# MineSweepers2019-Communcation.net
KiCad netlist of a schematic drawn in EAGLE
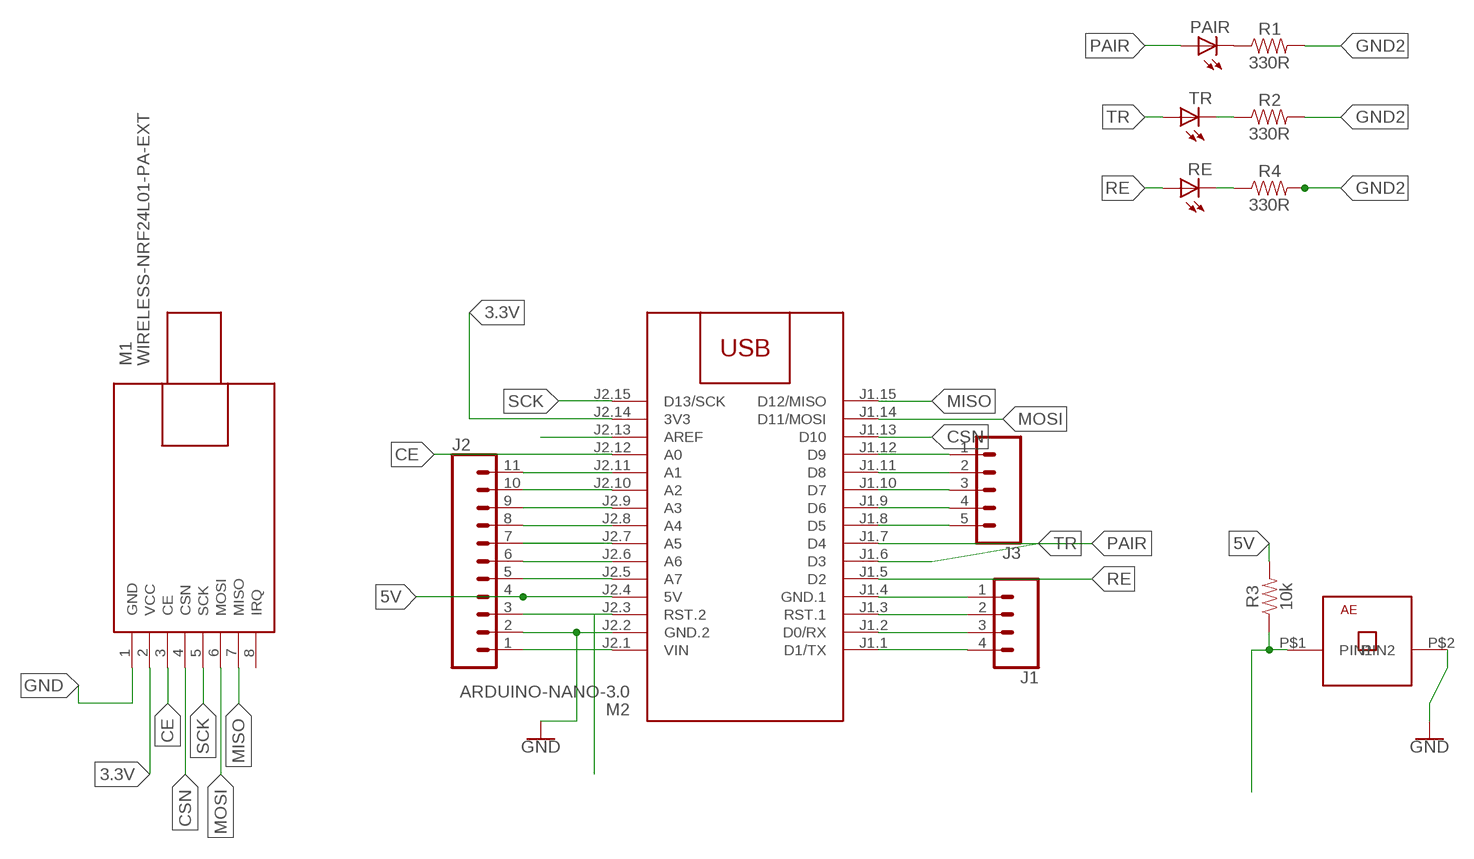
[diagram p0: schematic, sheet 1]

(export (version "E")
  (design (tool "Eeschema 10.0.6"))
  (components
    (comp (ref "J1")
      (value "CONN_04")
      (footprint "eagle-import:1X04")
      (libsource (lib "eagle-import") (part "CONN_04"))
    )
    (comp (ref "J2")
      (value "CONN_11")
      (footprint "eagle-import:1X11")
      (libsource (lib "eagle-import") (part "CONN_11"))
    )
    (comp (ref "J3")
      (value "CONN_05")
      (footprint "eagle-import:1X05")
      (libsource (lib "eagle-import") (part "CONN_05"))
    )
    (comp (ref "M1")
      (value "WIRELESS-NRF24L01-PA-EXT")
      (footprint "eagle-import:WIRELESS-NRF24L01-PA-EXT")
      (libsource (lib "eagle-import") (part "WIRELESS-NRF24L01-PA-EXT"))
    )
    (comp (ref "M2")
      (value "ARDUINO-NANO-3.0")
      (footprint "eagle-import:ARDUINO-NANO-3.0")
      (libsource (lib "eagle-import") (part "ARDUINO-NANO-3.0"))
    )
    (comp (ref "PAIR")
      (value "LED3MM")
      (footprint "eagle-import:LED3MM")
      (libsource (lib "eagle-import") (part "LED3MM"))
    )
    (comp (ref "R1")
      (value "330R")
      (footprint "eagle-import:AXIAL-0.3")
      (libsource (lib "eagle-import") (part "10MOHM-HORIZ-1/4W-5%"))
    )
    (comp (ref "R2")
      (value "330R")
      (footprint "eagle-import:AXIAL-0.3")
      (libsource (lib "eagle-import") (part "10MOHM-HORIZ-1/4W-5%"))
    )
    (comp (ref "R3")
      (value "10k")
      (footprint "eagle-import:AXIAL-0.3")
      (libsource (lib "eagle-import") (part "10MOHM-HORIZ-1/4W-5%"))
    )
    (comp (ref "R4")
      (value "330R")
      (footprint "eagle-import:AXIAL-0.3")
      (libsource (lib "eagle-import") (part "10MOHM-HORIZ-1/4W-5%"))
    )
    (comp (ref "RE")
      (value "LED3MM")
      (footprint "eagle-import:LED3MM")
      (libsource (lib "eagle-import") (part "LED3MM"))
    )
    (comp (ref "TR")
      (value "LED3MM")
      (footprint "eagle-import:LED3MM")
      (libsource (lib "eagle-import") (part "LED3MM"))
    )
    (comp (ref "U$1")
      (value "PUSHBUTTON-AE")
      (footprint "eagle-import:PUSHBUTTON-AE")
      (libsource (lib "eagle-import") (part "PUSHBUTTON-AE"))
    )
  )
  (nets
    (net (code "1") (name "3.3V") (class "Default")
      (node (ref "M1") (pin "2") (pinfunction "VCC_2") (pintype "power_in"))
      (node (ref "M2") (pin "J2.14") (pinfunction "3V3_J2.14") (pintype "power_in"))
    )
    (net (code "2") (name "5V") (class "Default")
      (node (ref "J2") (pin "4") (pinfunction "4_4") (pintype "passive"))
      (node (ref "M2") (pin "J2.4") (pinfunction "5V_J2.4") (pintype "power_in"))
      (node (ref "R3") (pin "P$2") (pinfunction "2_P$2") (pintype "passive"))
    )
    (net (code "3") (name "CE") (class "Default")
      (node (ref "M1") (pin "3") (pinfunction "CE_3") (pintype "bidirectional"))
      (node (ref "M2") (pin "J2.12") (pinfunction "A0_J2.12") (pintype "bidirectional"))
    )
    (net (code "4") (name "CSN") (class "Default")
      (node (ref "M1") (pin "4") (pinfunction "CSN_4") (pintype "bidirectional"))
      (node (ref "M2") (pin "J1.13") (pinfunction "D10_J1.13") (pintype "bidirectional"))
    )
    (net (code "5") (name "GND") (class "Default")
      (node (ref "J2") (pin "2") (pinfunction "2_2") (pintype "passive"))
      (node (ref "M1") (pin "1") (pinfunction "GND_1") (pintype "power_in"))
      (node (ref "M2") (pin "J2.2") (pinfunction "GND.2_J2.2") (pintype "power_in"))
      (node (ref "U$1") (pin "P$2") (pinfunction "PIN2_P$2") (pintype "bidirectional"))
    )
    (net (code "6") (name "GND2") (class "Default")
      (node (ref "J1") (pin "1") (pinfunction "1_1") (pintype "passive"))
      (node (ref "M2") (pin "J1.4") (pinfunction "GND.1_J1.4") (pintype "power_in"))
      (node (ref "R1") (pin "P$2") (pinfunction "2_P$2") (pintype "passive"))
      (node (ref "R2") (pin "P$2") (pinfunction "2_P$2") (pintype "passive"))
      (node (ref "R4") (pin "P$2") (pinfunction "2_P$2") (pintype "passive"))
    )
    (net (code "7") (name "MISO") (class "Default")
      (node (ref "M1") (pin "7") (pinfunction "MISO_7") (pintype "bidirectional"))
      (node (ref "M2") (pin "J1.15") (pinfunction "D12/MISO_J1.15") (pintype "bidirectional"))
    )
    (net (code "8") (name "MOSI") (class "Default")
      (node (ref "M1") (pin "6") (pinfunction "MOSI_6") (pintype "bidirectional"))
      (node (ref "M2") (pin "J1.14") (pinfunction "D11/MOSI_J1.14") (pintype "bidirectional"))
    )
    (net (code "9") (name "Net-(M2-A1)") (class "Default")
      (node (ref "J2") (pin "11") (pinfunction "11_11") (pintype "passive"))
      (node (ref "M2") (pin "J2.11") (pinfunction "A1_J2.11") (pintype "bidirectional"))
    )
    (net (code "10") (name "Net-(M2-A2)") (class "Default")
      (node (ref "J2") (pin "10") (pinfunction "10_10") (pintype "passive"))
      (node (ref "M2") (pin "J2.10") (pinfunction "A2_J2.10") (pintype "bidirectional"))
    )
    (net (code "11") (name "Net-(M2-A3)") (class "Default")
      (node (ref "J2") (pin "9") (pinfunction "9_9") (pintype "passive"))
      (node (ref "M2") (pin "J2.9") (pinfunction "A3_J2.9") (pintype "bidirectional"))
    )
    (net (code "12") (name "Net-(M2-A4)") (class "Default")
      (node (ref "J2") (pin "8") (pinfunction "8_8") (pintype "passive"))
      (node (ref "M2") (pin "J2.8") (pinfunction "A4_J2.8") (pintype "bidirectional"))
    )
    (net (code "13") (name "Net-(M2-A5)") (class "Default")
      (node (ref "J2") (pin "7") (pinfunction "7_7") (pintype "passive"))
      (node (ref "M2") (pin "J2.7") (pinfunction "A5_J2.7") (pintype "bidirectional"))
    )
    (net (code "14") (name "Net-(M2-A6)") (class "Default")
      (node (ref "J2") (pin "6") (pinfunction "6_6") (pintype "passive"))
      (node (ref "M2") (pin "J2.6") (pinfunction "A6_J2.6") (pintype "bidirectional"))
    )
    (net (code "15") (name "Net-(M2-A7)") (class "Default")
      (node (ref "J2") (pin "5") (pinfunction "5_5") (pintype "passive"))
      (node (ref "M2") (pin "J2.5") (pinfunction "A7_J2.5") (pintype "bidirectional"))
    )
    (net (code "16") (name "Net-(M2-D0{slash}RX)") (class "Default")
      (node (ref "J1") (pin "3") (pinfunction "3_3") (pintype "passive"))
      (node (ref "M2") (pin "J1.2") (pinfunction "D0/RX_J1.2") (pintype "bidirectional"))
    )
    (net (code "17") (name "Net-(M2-D1{slash}TX)") (class "Default")
      (node (ref "J1") (pin "4") (pinfunction "4_4") (pintype "passive"))
      (node (ref "M2") (pin "J1.1") (pinfunction "D1/TX_J1.1") (pintype "bidirectional"))
    )
    (net (code "18") (name "Net-(M2-D5)") (class "Default")
      (node (ref "J3") (pin "5") (pinfunction "5_5") (pintype "passive"))
      (node (ref "M2") (pin "J1.8") (pinfunction "D5_J1.8") (pintype "bidirectional"))
    )
    (net (code "19") (name "Net-(M2-D6)") (class "Default")
      (node (ref "J3") (pin "4") (pinfunction "4_4") (pintype "passive"))
      (node (ref "M2") (pin "J1.9") (pinfunction "D6_J1.9") (pintype "bidirectional"))
    )
    (net (code "20") (name "Net-(M2-D7)") (class "Default")
      (node (ref "J3") (pin "3") (pinfunction "3_3") (pintype "passive"))
      (node (ref "M2") (pin "J1.10") (pinfunction "D7_J1.10") (pintype "bidirectional"))
    )
    (net (code "21") (name "Net-(M2-D8)") (class "Default")
      (node (ref "J3") (pin "2") (pinfunction "2_2") (pintype "passive"))
      (node (ref "M2") (pin "J1.11") (pinfunction "D8_J1.11") (pintype "bidirectional"))
    )
    (net (code "22") (name "Net-(M2-D9)") (class "Default")
      (node (ref "J3") (pin "1") (pinfunction "1_1") (pintype "passive"))
      (node (ref "M2") (pin "J1.12") (pinfunction "D9_J1.12") (pintype "bidirectional"))
    )
    (net (code "23") (name "Net-(M2-RST.1)") (class "Default")
      (node (ref "J1") (pin "2") (pinfunction "2_2") (pintype "passive"))
      (node (ref "M2") (pin "J1.3") (pinfunction "RST.1_J1.3") (pintype "bidirectional"))
    )
    (net (code "24") (name "Net-(M2-RST.2)") (class "Default")
      (node (ref "J2") (pin "3") (pinfunction "3_3") (pintype "passive"))
      (node (ref "M2") (pin "J2.3") (pinfunction "RST.2_J2.3") (pintype "bidirectional"))
    )
    (net (code "25") (name "Net-(M2-VIN)") (class "Default")
      (node (ref "J2") (pin "1") (pinfunction "1_1") (pintype "passive"))
      (node (ref "M2") (pin "J2.1") (pinfunction "VIN_J2.1") (pintype "power_in"))
    )
    (net (code "26") (name "Net-(PAIR-C)") (class "Default")
      (node (ref "PAIR") (pin "K") (pinfunction "C_K") (pintype "passive"))
      (node (ref "R1") (pin "P$1") (pinfunction "1_P$1") (pintype "passive"))
    )
    (net (code "27") (name "Net-(R2-1)") (class "Default")
      (node (ref "R2") (pin "P$1") (pinfunction "1_P$1") (pintype "passive"))
      (node (ref "TR") (pin "K") (pinfunction "C_K") (pintype "passive"))
    )
    (net (code "28") (name "Net-(R3-1)") (class "Default")
      (node (ref "R3") (pin "P$1") (pinfunction "1_P$1") (pintype "passive"))
      (node (ref "U$1") (pin "P$1") (pinfunction "PIN1_P$1") (pintype "bidirectional"))
    )
    (net (code "29") (name "Net-(R4-1)") (class "Default")
      (node (ref "R4") (pin "P$1") (pinfunction "1_P$1") (pintype "passive"))
      (node (ref "RE") (pin "K") (pinfunction "C_K") (pintype "passive"))
    )
    (net (code "30") (name "PAIR") (class "Default")
      (node (ref "M2") (pin "J1.7") (pinfunction "D4_J1.7") (pintype "bidirectional"))
      (node (ref "PAIR") (pin "A") (pinfunction "A_A") (pintype "passive"))
    )
    (net (code "31") (name "RE") (class "Default")
      (node (ref "M2") (pin "J1.5") (pinfunction "D2_J1.5") (pintype "bidirectional"))
      (node (ref "RE") (pin "A") (pinfunction "A_A") (pintype "passive"))
    )
    (net (code "32") (name "SCK") (class "Default")
      (node (ref "M1") (pin "5") (pinfunction "SCK_5") (pintype "bidirectional"))
      (node (ref "M2") (pin "J2.15") (pinfunction "D13/SCK_J2.15") (pintype "bidirectional"))
    )
    (net (code "33") (name "TR") (class "Default")
      (node (ref "M2") (pin "J1.6") (pinfunction "D3_J1.6") (pintype "bidirectional"))
      (node (ref "TR") (pin "A") (pinfunction "A_A") (pintype "passive"))
    )
    (net (code "34") (name "unconnected-(M1-IRQ-Pad8)") (class "Default")
      (node (ref "M1") (pin "8") (pinfunction "IRQ_8") (pintype "bidirectional"))
    )
    (net (code "35") (name "unconnected-(M2-AREF-PadJ2.13)") (class "Default")
      (node (ref "M2") (pin "J2.13") (pinfunction "AREF_J2.13") (pintype "bidirectional"))
    )
  )
)
